# Sheet1.net
KiCad netlist of a schematic drawn in Altium Designer
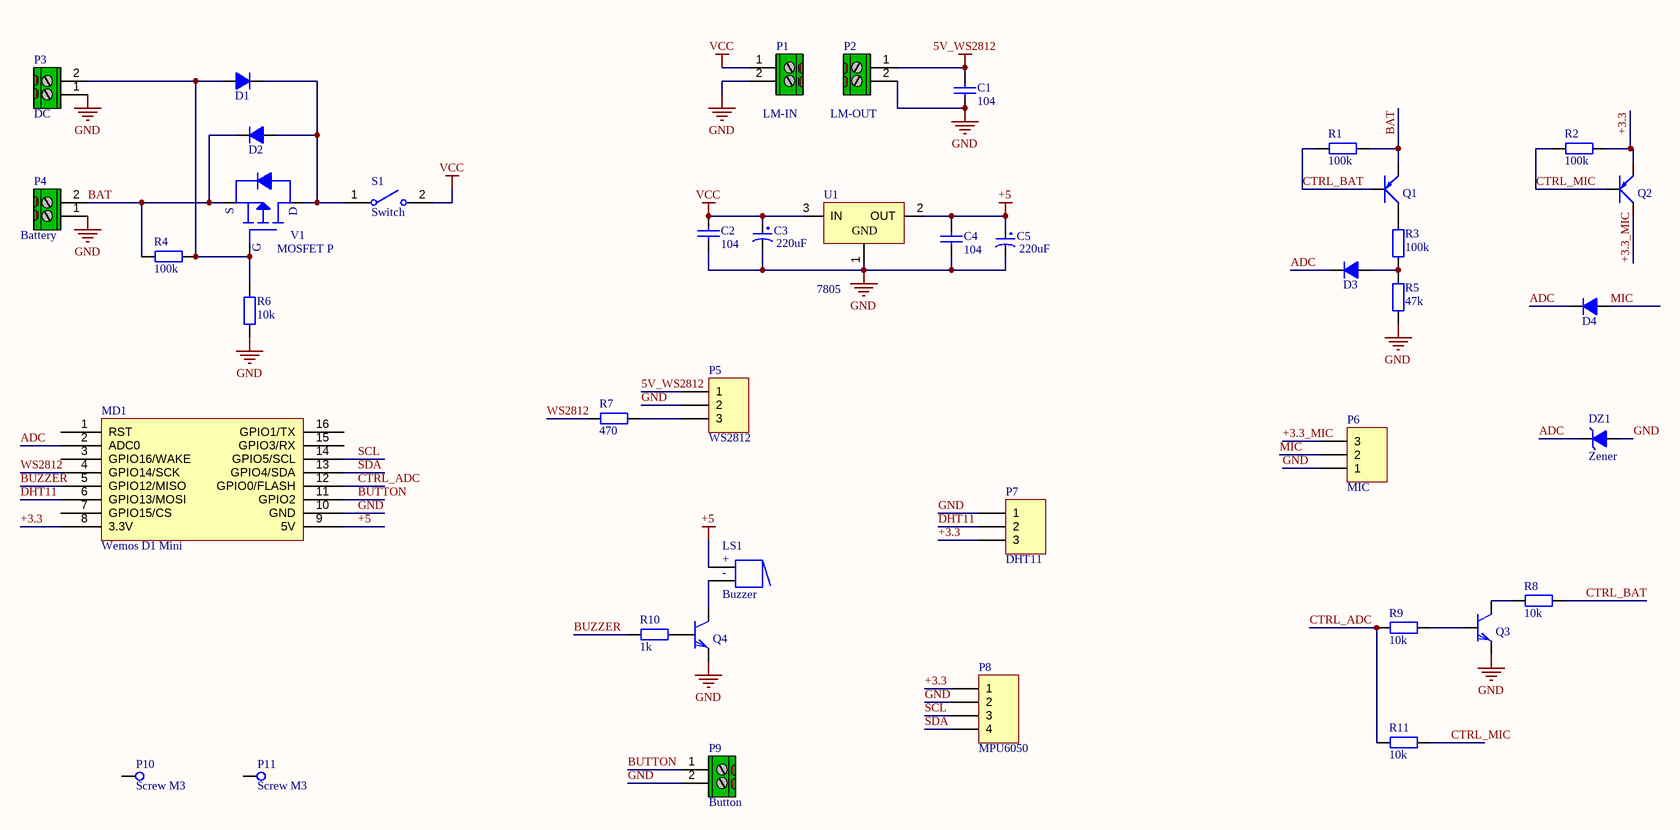
[diagram p0: Sheet1.SchDoc]

(export (version "E")
  (design (tool "Eeschema 10.0.6"))
  (components
    (comp (ref "C1")
      (value "104")
      (footprint "CAP [0805]")
      (description "Cap")
      (libsource (lib "VietKynlLib") (part "Tu"))
    )
    (comp (ref "C2")
      (value "104")
      (footprint "CAP [0805]")
      (description "Cap")
      (libsource (lib "VietKynlLib") (part "Tu"))
    )
    (comp (ref "C3")
      (value "220uF")
      (footprint "TU HOA 8mm")
      (description "dip")
      (libsource (lib "VietKynlLib") (part "TU HOA"))
    )
    (comp (ref "C4")
      (value "104")
      (footprint "CAP [0805]")
      (description "Cap")
      (libsource (lib "VietKynlLib") (part "Tu"))
    )
    (comp (ref "C5")
      (value "220uF")
      (footprint "TU HOA 8mm")
      (description "dip")
      (libsource (lib "VietKynlLib") (part "TU HOA"))
    )
    (comp (ref "D1")
      (value "Diode")
      (footprint "DIODE 10.5MM")
      (fields (field (name "PUBLISHER") "Altium Limited"))
      (libsource (lib "VietKynlLib") (part "Diode"))
    )
    (comp (ref "D2")
      (value "Diode")
      (footprint "DIODE 10.5MM")
      (fields (field (name "PUBLISHER") "Altium Limited"))
      (libsource (lib "VietKynlLib") (part "Diode"))
    )
    (comp (ref "D3")
      (value "Diode")
      (footprint "DIODE SMD 5.5MM")
      (fields (field (name "PUBLISHER") "Altium Limited"))
      (libsource (lib "VietKynlLib") (part "Diode"))
    )
    (comp (ref "D4")
      (value "Diode")
      (footprint "DIODE SMD 5.5MM")
      (fields (field (name "PUBLISHER") "Altium Limited"))
      (libsource (lib "VietKynlLib") (part "Diode"))
    )
    (comp (ref "DZ1")
      (value "Zener")
      (footprint "DIODE SMD 3.8MM")
      (libsource (lib "VietKynlLib") (part "Zener"))
    )
    (comp (ref "LS1")
      (value "Buzzer")
      (footprint "Buzzer sounder 14mm")
      (description "Magnetic Transducer Buzzer")
      (fields (field (name "PUBLISHER") "Altium Limited"))
      (libsource (lib "VietKynlLib") (part "Buzzer"))
    )
    (comp (ref "MD1")
      (value "Wemos D1 Mini")
      (footprint "Wemos D1 Mini")
      (libsource (lib "VietKynlLib") (part "Wemos D1 Mini"))
    )
    (comp (ref "P1")
      (value "LM-IN")
      (footprint "TEST PAD - medium")
      (description "Header, 2-Pin")
      (fields (field (name "PUBLISHER") "Altium Limited"))
      (libsource (lib "VietKynlLib") (part "CON2"))
    )
    (comp (ref "P2")
      (value "LM-OUT")
      (footprint "TEST PAD - medium")
      (description "Header, 2-Pin")
      (fields (field (name "PUBLISHER") "Altium Limited"))
      (libsource (lib "") (part "CON2_1"))
    )
    (comp (ref "P3")
      (value "DC")
      (footprint "TEST PAD - medium")
      (description "Header, 2-Pin")
      (fields (field (name "PUBLISHER") "Altium Limited"))
      (libsource (lib "") (part "CON2_2"))
    )
    (comp (ref "P4")
      (value "Battery")
      (footprint "TEST PAD - medium")
      (description "Header, 2-Pin")
      (fields (field (name "PUBLISHER") "Altium Limited"))
      (libsource (lib "") (part "CON2_2"))
    )
    (comp (ref "P5")
      (value "WS2812")
      (footprint "Header3")
      (description "Header, 3-Pin")
      (fields (field (name "PUBLISHER") "Altium Limited"))
      (libsource (lib "VietKynlLib") (part "CON3"))
    )
    (comp (ref "P6")
      (value "MIC")
      (footprint "Header3")
      (description "Header, 3-Pin")
      (fields (field (name "PUBLISHER") "Altium Limited"))
      (libsource (lib "") (part "CON3_1"))
    )
    (comp (ref "P7")
      (value "DHT11")
      (footprint "Header3")
      (description "Header, 3-Pin")
      (fields (field (name "PUBLISHER") "Altium Limited"))
      (libsource (lib "VietKynlLib") (part "CON3"))
    )
    (comp (ref "P8")
      (value "MPU6050")
      (footprint "Header4")
      (description "Header, 4-Pin")
      (fields (field (name "PUBLISHER") "Altium Limited"))
      (libsource (lib "VietKynlLib") (part "CON4"))
    )
    (comp (ref "P9")
      (value "Button")
      (footprint "Header2")
      (description "Header, 2-Pin")
      (fields (field (name "PUBLISHER") "Altium Limited"))
      (libsource (lib "VietKynlLib") (part "CON2"))
    )
    (comp (ref "P10")
      (value "Screw M3")
      (footprint "JP SCREW M3x10")
      (description "Connect Pad, 1-Pin")
      (fields (field (name "PUBLISHER") "Altium Limited"))
      (libsource (lib "VietKynlLib") (part "CON1"))
    )
    (comp (ref "P11")
      (value "Screw M3")
      (footprint "JP SCREW M3x10")
      (description "Connect Pad, 1-Pin")
      (fields (field (name "PUBLISHER") "Altium Limited"))
      (libsource (lib "VietKynlLib") (part "CON1"))
    )
    (comp (ref "Q1")
      (value "A1015")
      (footprint "VietKynlLib:SOT23")
      (description "A1015 SMD")
      (fields (field (name "PUBLISHER") "Hoang Nguyen"))
      (libsource (lib "VietKynlLib") (part "A1015 SMD"))
    )
    (comp (ref "Q2")
      (value "A1015")
      (footprint "VietKynlLib:SOT23")
      (description "A1015 SMD")
      (fields (field (name "PUBLISHER") "Hoang Nguyen"))
      (libsource (lib "VietKynlLib") (part "A1015 SMD"))
    )
    (comp (ref "Q3")
      (value "C1815")
      (footprint "VietKynlLib:SOT23")
      (description "C1815 SMD")
      (fields (field (name "PUBLISHER") "Viet Kynl"))
      (libsource (lib "VietKynlLib") (part "C1815 SMD"))
    )
    (comp (ref "Q4")
      (value "C1815")
      (footprint "VietKynlLib:SOT23")
      (description "C1815 SMD")
      (fields (field (name "PUBLISHER") "Viet Kynl"))
      (libsource (lib "VietKynlLib") (part "C1815 SMD"))
    )
    (comp (ref "R1")
      (value "100k")
      (footprint "VietKynlLib:RES [0805]")
      (description "Resistor")
      (libsource (lib "VietKynlLib") (part "Tro"))
    )
    (comp (ref "R2")
      (value "100k")
      (footprint "VietKynlLib:RES [0805]")
      (description "Resistor")
      (libsource (lib "VietKynlLib") (part "Tro"))
    )
    (comp (ref "R3")
      (value "100k")
      (footprint "VietKynlLib:RES [0805]")
      (description "Resistor")
      (libsource (lib "VietKynlLib") (part "Tro"))
    )
    (comp (ref "R4")
      (value "100k")
      (footprint "VietKynlLib:RES [0805]")
      (description "Resistor")
      (libsource (lib "VietKynlLib") (part "Tro"))
    )
    (comp (ref "R5")
      (value "47k")
      (footprint "VietKynlLib:RES [0805]")
      (description "Resistor")
      (libsource (lib "VietKynlLib") (part "Tro"))
    )
    (comp (ref "R6")
      (value "10k")
      (footprint "VietKynlLib:RES [0805]")
      (description "Resistor")
      (libsource (lib "VietKynlLib") (part "Tro"))
    )
    (comp (ref "R7")
      (value "470")
      (footprint "VietKynlLib:RES [0805]")
      (description "Resistor")
      (libsource (lib "VietKynlLib") (part "Tro"))
    )
    (comp (ref "R8")
      (value "10k")
      (footprint "VietKynlLib:RES [0805]")
      (description "Resistor")
      (libsource (lib "VietKynlLib") (part "Tro"))
    )
    (comp (ref "R9")
      (value "10k")
      (footprint "VietKynlLib:RES [0805]")
      (description "Resistor")
      (libsource (lib "VietKynlLib") (part "Tro"))
    )
    (comp (ref "R10")
      (value "1k")
      (footprint "VietKynlLib:RES [0805]")
      (description "Resistor")
      (libsource (lib "VietKynlLib") (part "Tro"))
    )
    (comp (ref "R11")
      (value "10k")
      (footprint "VietKynlLib:RES [0805]")
      (description "Resistor")
      (libsource (lib "VietKynlLib") (part "Tro"))
    )
    (comp (ref "S1")
      (value "Switch")
      (footprint "TEST PAD - medium")
      (fields (field (name "PUBLISHER") "Altium Limited"))
      (libsource (lib "VietKynlLib") (part "Switch"))
    )
    (comp (ref "U1")
      (value "7805")
      (footprint "TO252 SMD")
      (description "3-Terminal 1A Positive Voltage Regulator")
      (libsource (lib "VietKynlLib") (part "7805"))
    )
    (comp (ref "V1")
      (value "MOSFET P")
      (footprint "VietKynlLib:TO252 SMD")
      (description "P-CHANNEL POWER MOSFETS")
      (fields (field (name "PUBLISHER") "Hoang Nguyen"))
      (libsource (lib "VietKynlLib") (part "MOSFET P"))
    )
  )
  (nets
    (net (code "1") (name "+5") (class "Default")
      (node (ref "C4") (pin "2") (pinfunction "2_2") (pintype "passive"))
      (node (ref "C5") (pin "1") (pinfunction "1_1") (pintype "passive"))
      (node (ref "LS1") (pin "1") (pinfunction "+_1") (pintype "passive"))
      (node (ref "MD1") (pin "9") (pinfunction "5V_9") (pintype "passive"))
      (node (ref "U1") (pin "2") (pinfunction "OUT_2") (pintype "passive"))
    )
    (net (code "2") (name "/+3.3") (class "Default")
      (node (ref "MD1") (pin "8") (pinfunction "3.3V_8") (pintype "passive"))
      (node (ref "P7") (pin "3") (pinfunction "3_3") (pintype "passive"))
      (node (ref "P8") (pin "1") (pinfunction "1_1") (pintype "passive"))
      (node (ref "Q2") (pin "2") (pinfunction "E_2") (pintype "passive"))
      (node (ref "R2") (pin "2") (pinfunction "2_2") (pintype "passive"))
    )
    (net (code "3") (name "/+3.3_MIC") (class "Default")
      (node (ref "P6") (pin "3") (pinfunction "3_3") (pintype "passive"))
      (node (ref "Q2") (pin "3") (pinfunction "C_3") (pintype "passive"))
    )
    (net (code "4") (name "/ADC") (class "Default")
      (node (ref "D3") (pin "2") (pinfunction "K_2") (pintype "passive"))
      (node (ref "D4") (pin "2") (pinfunction "K_2") (pintype "passive"))
      (node (ref "DZ1") (pin "2") (pinfunction "K_2") (pintype "passive"))
      (node (ref "MD1") (pin "2") (pinfunction "ADC0_2") (pintype "passive"))
    )
    (net (code "5") (name "/BAT") (class "Default")
      (node (ref "D2") (pin "2") (pinfunction "K_2") (pintype "passive"))
      (node (ref "P4") (pin "2") (pinfunction "2_2") (pintype "passive"))
      (node (ref "Q1") (pin "2") (pinfunction "E_2") (pintype "passive"))
      (node (ref "R1") (pin "2") (pinfunction "2_2") (pintype "passive"))
      (node (ref "R4") (pin "1") (pinfunction "1_1") (pintype "passive"))
      (node (ref "V1") (pin "3") (pinfunction "S_3") (pintype "passive"))
    )
    (net (code "6") (name "/BUTTON") (class "Default")
      (node (ref "MD1") (pin "11") (pinfunction "GPIO2_11") (pintype "passive"))
      (node (ref "P9") (pin "1") (pinfunction "1_1") (pintype "passive"))
    )
    (net (code "7") (name "/BUZZER") (class "Default")
      (node (ref "MD1") (pin "5") (pinfunction "GPIO12/MISO_5") (pintype "passive"))
      (node (ref "R10") (pin "1") (pinfunction "1_1") (pintype "passive"))
    )
    (net (code "8") (name "/CTRL_ADC") (class "Default")
      (node (ref "MD1") (pin "12") (pinfunction "GPIO0/FLASH_12") (pintype "passive"))
      (node (ref "R11") (pin "2") (pinfunction "2_2") (pintype "passive"))
      (node (ref "R9") (pin "2") (pinfunction "2_2") (pintype "passive"))
    )
    (net (code "9") (name "/CTRL_BAT") (class "Default")
      (node (ref "Q1") (pin "1") (pinfunction "B_1") (pintype "passive"))
      (node (ref "R1") (pin "1") (pinfunction "1_1") (pintype "passive"))
      (node (ref "R8") (pin "1") (pinfunction "1_1") (pintype "passive"))
    )
    (net (code "10") (name "/CTRL_MIC") (class "Default")
      (node (ref "Q2") (pin "1") (pinfunction "B_1") (pintype "passive"))
      (node (ref "R11") (pin "1") (pinfunction "1_1") (pintype "passive"))
      (node (ref "R2") (pin "1") (pinfunction "1_1") (pintype "passive"))
    )
    (net (code "11") (name "/DHT11") (class "Default")
      (node (ref "MD1") (pin "6") (pinfunction "GPIO13/MOSI_6") (pintype "passive"))
      (node (ref "P7") (pin "2") (pinfunction "2_2") (pintype "passive"))
    )
    (net (code "12") (name "/MIC") (class "Default")
      (node (ref "D4") (pin "1") (pinfunction "A_1") (pintype "passive"))
      (node (ref "P6") (pin "2") (pinfunction "2_2") (pintype "passive"))
    )
    (net (code "13") (name "/SCL") (class "Default")
      (node (ref "MD1") (pin "14") (pinfunction "GPIO5/SCL_14") (pintype "passive"))
      (node (ref "P8") (pin "3") (pinfunction "3_3") (pintype "passive"))
    )
    (net (code "14") (name "/SDA") (class "Default")
      (node (ref "MD1") (pin "13") (pinfunction "GPIO4/SDA_13") (pintype "passive"))
      (node (ref "P8") (pin "4") (pinfunction "4_4") (pintype "passive"))
    )
    (net (code "15") (name "/WS2812") (class "Default")
      (node (ref "MD1") (pin "4") (pinfunction "GPIO14/SCK_4") (pintype "passive"))
      (node (ref "R7") (pin "1") (pinfunction "1_1") (pintype "passive"))
    )
    (net (code "16") (name "5V_WS2812") (class "Default")
      (node (ref "C1") (pin "2") (pinfunction "2_2") (pintype "passive"))
      (node (ref "P2") (pin "1") (pinfunction "1_1") (pintype "passive"))
      (node (ref "P5") (pin "1") (pinfunction "1_1") (pintype "passive"))
    )
    (net (code "17") (name "GND") (class "Default")
      (node (ref "C1") (pin "1") (pinfunction "1_1") (pintype "passive"))
      (node (ref "C2") (pin "1") (pinfunction "1_1") (pintype "passive"))
      (node (ref "C3") (pin "2") (pinfunction "2_2") (pintype "passive"))
      (node (ref "C4") (pin "1") (pinfunction "1_1") (pintype "passive"))
      (node (ref "C5") (pin "2") (pinfunction "2_2") (pintype "passive"))
      (node (ref "DZ1") (pin "1") (pinfunction "A_1") (pintype "passive"))
      (node (ref "MD1") (pin "10") (pinfunction "GND_10") (pintype "passive"))
      (node (ref "P1") (pin "2") (pinfunction "2_2") (pintype "passive"))
      (node (ref "P2") (pin "2") (pinfunction "2_2") (pintype "passive"))
      (node (ref "P3") (pin "1") (pinfunction "1_1") (pintype "passive"))
      (node (ref "P4") (pin "1") (pinfunction "1_1") (pintype "passive"))
      (node (ref "P5") (pin "2") (pinfunction "2_2") (pintype "passive"))
      (node (ref "P6") (pin "1") (pinfunction "1_1") (pintype "passive"))
      (node (ref "P7") (pin "1") (pinfunction "1_1") (pintype "passive"))
      (node (ref "P8") (pin "2") (pinfunction "2_2") (pintype "passive"))
      (node (ref "P9") (pin "2") (pinfunction "2_2") (pintype "passive"))
      (node (ref "Q3") (pin "2") (pinfunction "E_2") (pintype "passive"))
      (node (ref "Q4") (pin "2") (pinfunction "E_2") (pintype "passive"))
      (node (ref "R5") (pin "1") (pinfunction "1_1") (pintype "passive"))
      (node (ref "R6") (pin "1") (pinfunction "1_1") (pintype "passive"))
      (node (ref "U1") (pin "1") (pinfunction "GND_1") (pintype "passive"))
    )
    (net (code "18") (name "Net-(D1-A)") (class "Default")
      (node (ref "D1") (pin "1") (pinfunction "A_1") (pintype "passive"))
      (node (ref "P3") (pin "2") (pinfunction "2_2") (pintype "passive"))
      (node (ref "R4") (pin "2") (pinfunction "2_2") (pintype "passive"))
      (node (ref "R6") (pin "2") (pinfunction "2_2") (pintype "passive"))
      (node (ref "V1") (pin "1") (pinfunction "G_1") (pintype "passive"))
    )
    (net (code "19") (name "Net-(D1-K)") (class "Default")
      (node (ref "D1") (pin "2") (pinfunction "K_2") (pintype "passive"))
      (node (ref "D2") (pin "1") (pinfunction "A_1") (pintype "passive"))
      (node (ref "S1") (pin "1") (pinfunction "1_1") (pintype "passive"))
      (node (ref "V1") (pin "2") (pinfunction "D_2") (pintype "passive"))
    )
    (net (code "20") (name "Net-(D3-A)") (class "Default")
      (node (ref "D3") (pin "1") (pinfunction "A_1") (pintype "passive"))
      (node (ref "R3") (pin "1") (pinfunction "1_1") (pintype "passive"))
      (node (ref "R5") (pin "2") (pinfunction "2_2") (pintype "passive"))
    )
    (net (code "21") (name "Net-(P5-Pad3)") (class "Default")
      (node (ref "P5") (pin "3") (pinfunction "3_3") (pintype "passive"))
      (node (ref "R7") (pin "2") (pinfunction "2_2") (pintype "passive"))
    )
    (net (code "22") (name "Net-(Q1-C)") (class "Default")
      (node (ref "Q1") (pin "3") (pinfunction "C_3") (pintype "passive"))
      (node (ref "R3") (pin "2") (pinfunction "2_2") (pintype "passive"))
    )
    (net (code "23") (name "Net-(Q3-B)") (class "Default")
      (node (ref "Q3") (pin "1") (pinfunction "B_1") (pintype "passive"))
      (node (ref "R9") (pin "1") (pinfunction "1_1") (pintype "passive"))
    )
    (net (code "24") (name "Net-(Q3-C)") (class "Default")
      (node (ref "Q3") (pin "3") (pinfunction "C_3") (pintype "passive"))
      (node (ref "R8") (pin "2") (pinfunction "2_2") (pintype "passive"))
    )
    (net (code "25") (name "Net-(Q4-B)") (class "Default")
      (node (ref "Q4") (pin "1") (pinfunction "B_1") (pintype "passive"))
      (node (ref "R10") (pin "2") (pinfunction "2_2") (pintype "passive"))
    )
    (net (code "26") (name "Net-(Q4-C)") (class "Default")
      (node (ref "LS1") (pin "2") (pinfunction "2_2") (pintype "passive"))
      (node (ref "Q4") (pin "3") (pinfunction "C_3") (pintype "passive"))
    )
    (net (code "27") (name "VCC") (class "Default")
      (node (ref "C2") (pin "2") (pinfunction "2_2") (pintype "passive"))
      (node (ref "C3") (pin "1") (pinfunction "1_1") (pintype "passive"))
      (node (ref "P1") (pin "1") (pinfunction "1_1") (pintype "passive"))
      (node (ref "S1") (pin "2") (pinfunction "2_2") (pintype "passive"))
      (node (ref "U1") (pin "3") (pinfunction "IN_3") (pintype "passive"))
    )
    (net (code "28") (name "unconnected-(MD1-GPIO1{slash}TX-Pad16)") (class "Default")
      (node (ref "MD1") (pin "16") (pinfunction "GPIO1/TX_16") (pintype "passive"))
    )
    (net (code "29") (name "unconnected-(MD1-GPIO3{slash}RX-Pad15)") (class "Default")
      (node (ref "MD1") (pin "15") (pinfunction "GPIO3/RX_15") (pintype "passive"))
    )
    (net (code "30") (name "unconnected-(MD1-GPIO15{slash}CS-Pad7)") (class "Default")
      (node (ref "MD1") (pin "7") (pinfunction "GPIO15/CS_7") (pintype "passive"))
    )
    (net (code "31") (name "unconnected-(MD1-GPIO16{slash}WAKE-Pad3)") (class "Default")
      (node (ref "MD1") (pin "3") (pinfunction "GPIO16/WAKE_3") (pintype "passive"))
    )
    (net (code "32") (name "unconnected-(MD1-RST-Pad1)") (class "Default")
      (node (ref "MD1") (pin "1") (pinfunction "RST_1") (pintype "passive"))
    )
    (net (code "33") (name "unconnected-(P10-CP-Pad1)") (class "Default")
      (node (ref "P10") (pin "1") (pinfunction "CP_1") (pintype "passive"))
    )
    (net (code "34") (name "unconnected-(P11-CP-Pad1)") (class "Default")
      (node (ref "P11") (pin "1") (pinfunction "CP_1") (pintype "passive"))
    )
  )
)
